# Sheet1.net
KiCad netlist of a schematic drawn in Altium Designer
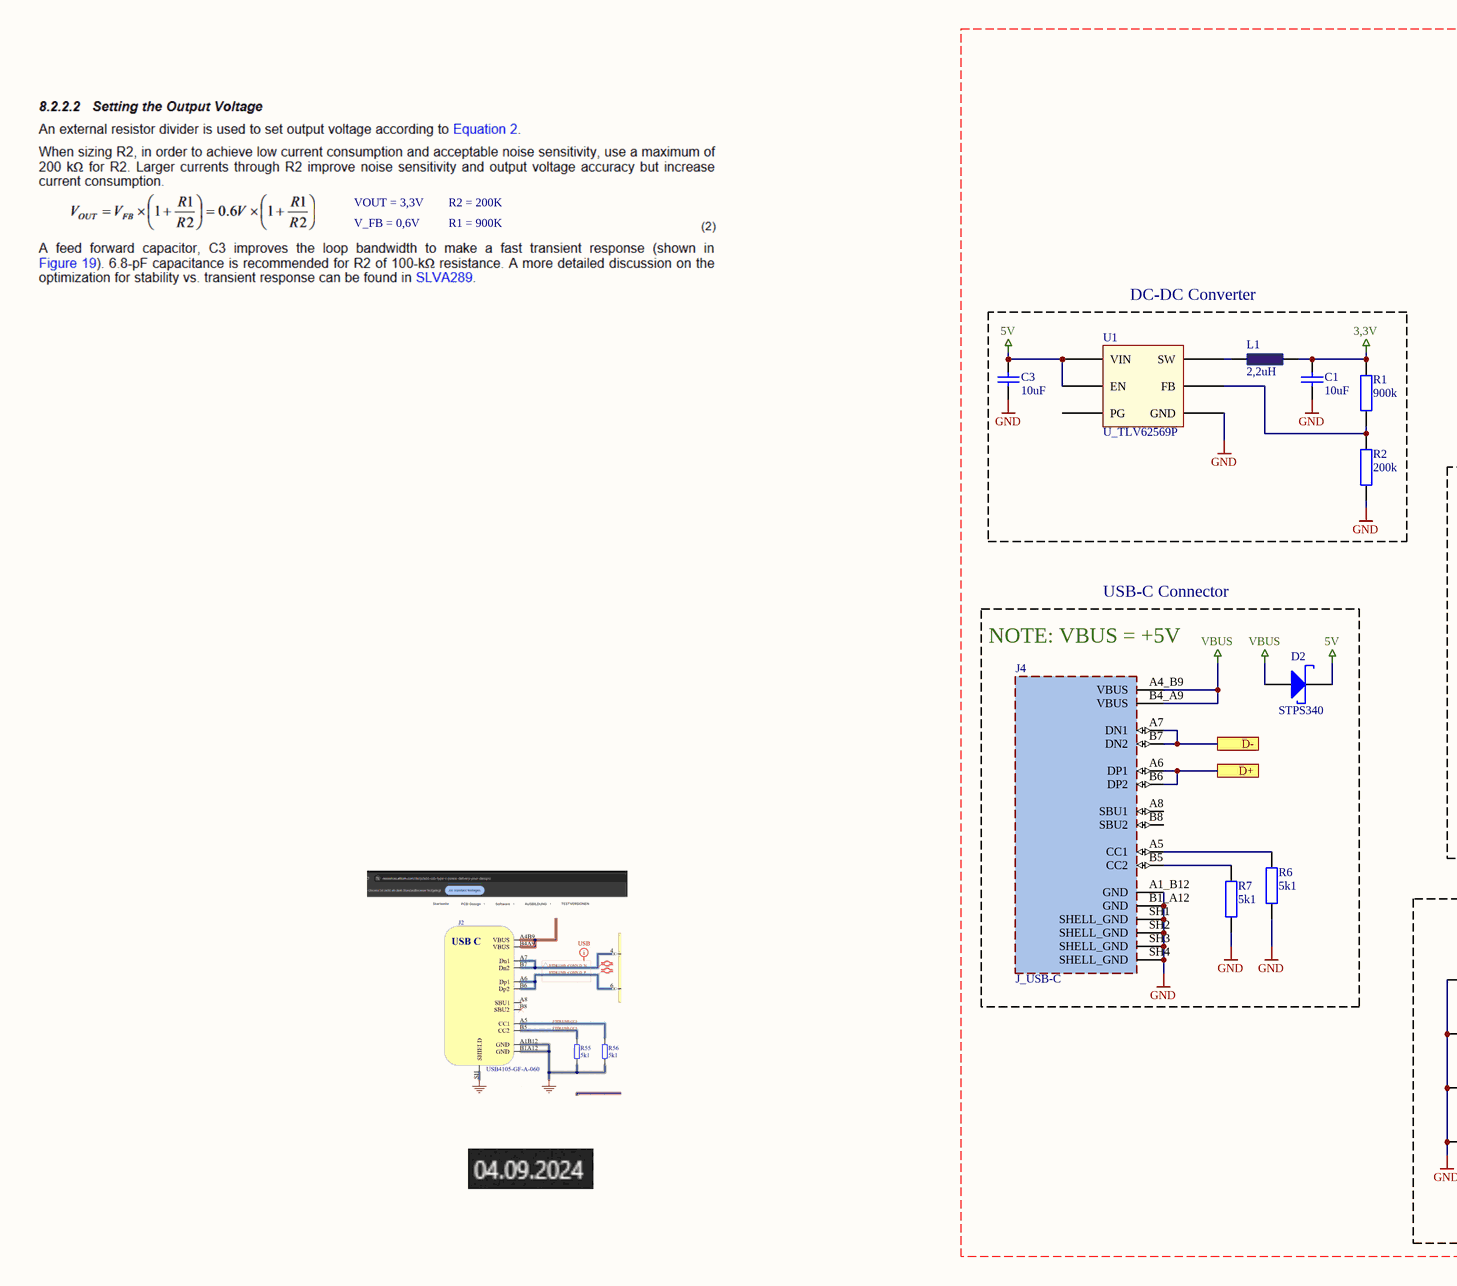
[diagram p0: Sheet1.SchDoc, left]
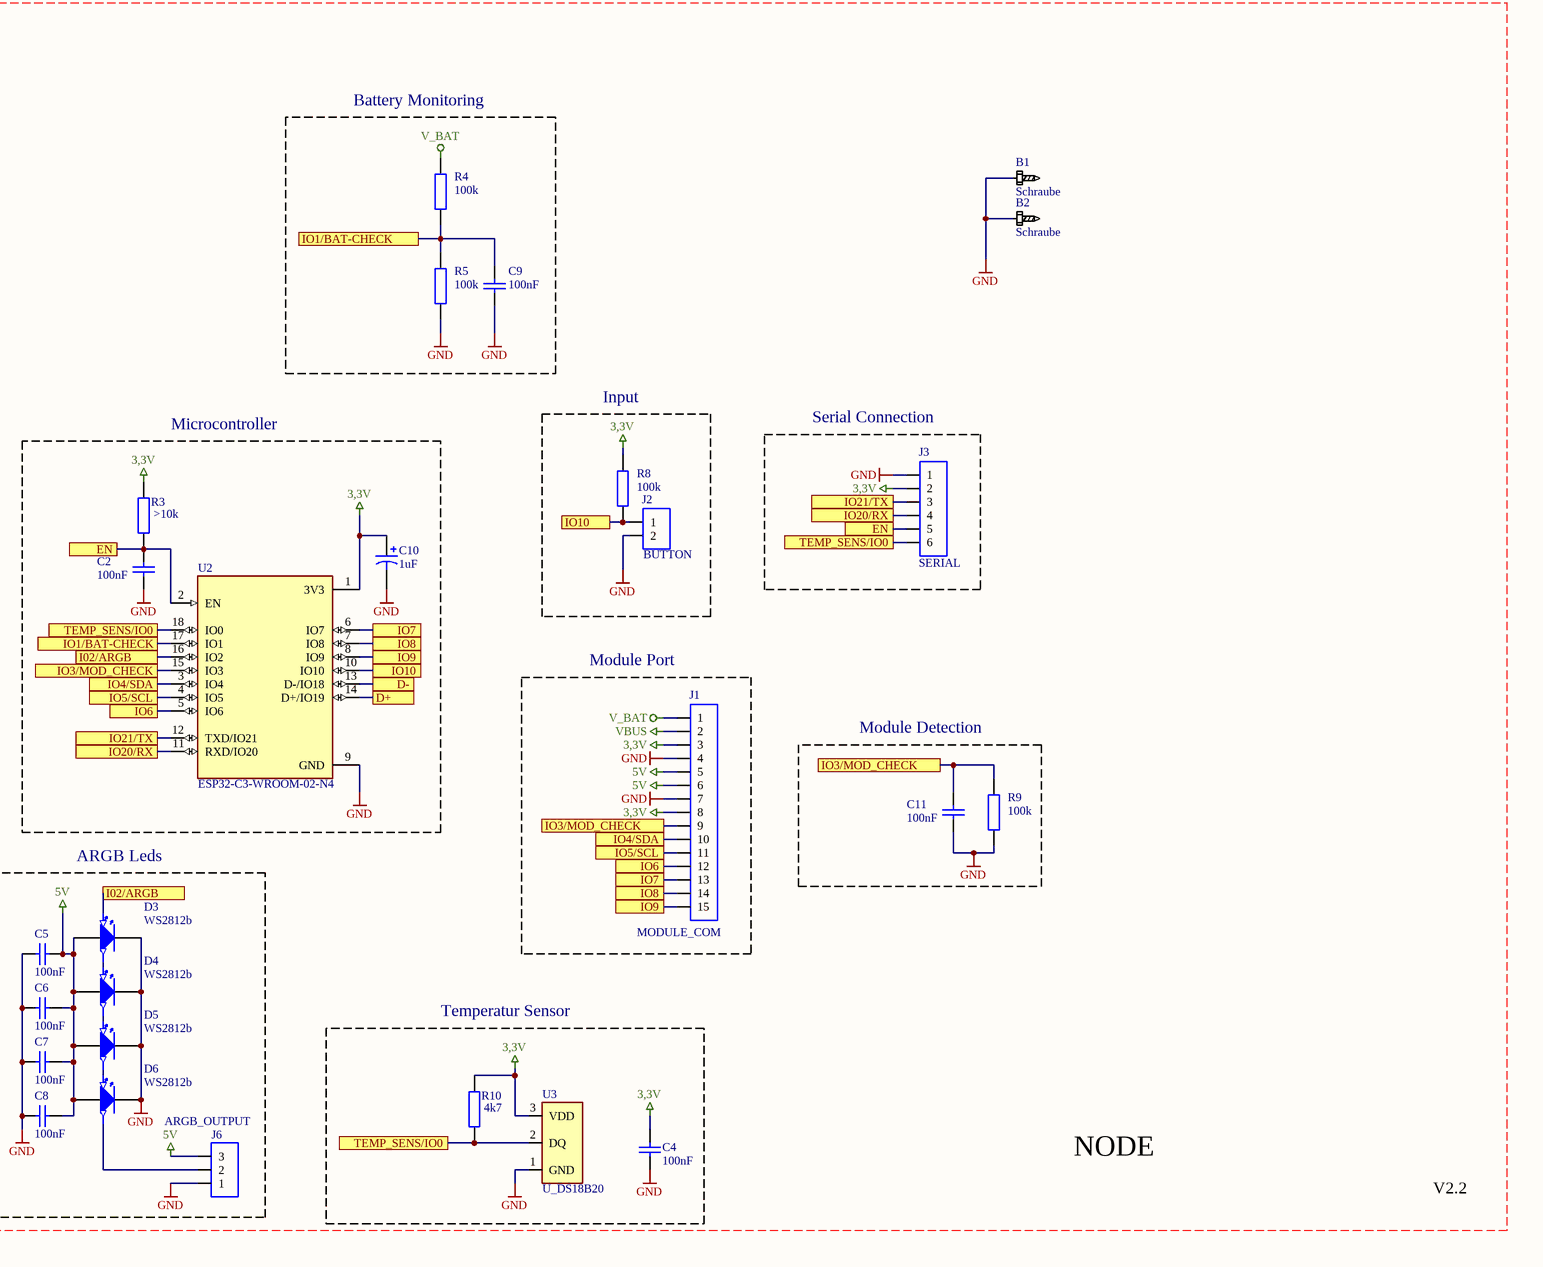
[diagram p1: Sheet1.SchDoc, right]

(export (version "E")
  (design (tool "Eeschema 10.0.6"))
  (components
    (comp (ref "B1")
      (value "Schraube")
      (footprint "B_Schraube-M3 PAD")
      (description "Schraubenloch für M3 Schrauben")
      (libsource (lib "SCHLIB-PCSB_5.1.3") (part "B_Schraube"))
    )
    (comp (ref "B2")
      (value "Schraube")
      (footprint "B_Schraube-M3 PAD")
      (description "Schraubenloch für M3 Schrauben")
      (libsource (lib "SCHLIB-PCSB_5.1.3") (part "B_Schraube"))
    )
    (comp (ref "C1")
      (value "10uF")
      (footprint "C_SMD_0805")
      (description "Kondensator SMD Universal, Keramik, Folie, usw.")
      (libsource (lib "SCHLIB-PCSB_5.1.3") (part "C_SMD_KO"))
    )
    (comp (ref "C2")
      (value "100nF")
      (footprint "C_SMD_0603")
      (description "Kondensator SMD Universal, Keramik, Folie, usw.")
      (libsource (lib "SCHLIB-PCSB_5.1.3") (part "C_SMD_KO"))
    )
    (comp (ref "C3")
      (value "10uF")
      (footprint "C_SMD_0805")
      (description "Kondensator SMD Universal, Keramik, Folie, usw.")
      (libsource (lib "SCHLIB-PCSB_5.1.3") (part "C_SMD_KO"))
    )
    (comp (ref "C4")
      (value "100nF")
      (footprint "C_SMD_0603")
      (description "Kondensator SMD Universal, Keramik, Folie, usw.")
      (libsource (lib "SCHLIB-PCSB_5.1.3") (part "C_SMD_KO"))
    )
    (comp (ref "C5")
      (value "100nF")
      (footprint "C_SMD_0603")
      (description "Kondensator SMD Universal, Keramik, Folie, usw.")
      (libsource (lib "SCHLIB-PCSB_5.1.3") (part "C_SMD_KO"))
    )
    (comp (ref "C6")
      (value "100nF")
      (footprint "C_SMD_0603")
      (description "Kondensator SMD Universal, Keramik, Folie, usw.")
      (libsource (lib "SCHLIB-PCSB_5.1.3") (part "C_SMD_KO"))
    )
    (comp (ref "C7")
      (value "100nF")
      (footprint "C_SMD_0603")
      (description "Kondensator SMD Universal, Keramik, Folie, usw.")
      (libsource (lib "SCHLIB-PCSB_5.1.3") (part "C_SMD_KO"))
    )
    (comp (ref "C8")
      (value "100nF")
      (footprint "C_SMD_0603")
      (description "Kondensator SMD Universal, Keramik, Folie, usw.")
      (libsource (lib "SCHLIB-PCSB_5.1.3") (part "C_SMD_KO"))
    )
    (comp (ref "C9")
      (value "100nF")
      (footprint "C_SMD_0603")
      (description "Kondensator SMD Universal, Keramik, Folie, usw.")
      (libsource (lib "SCHLIB-PCSB_5.1.3") (part "C_SMD_KO"))
    )
    (comp (ref "C10")
      (value "1uF")
      (footprint "C_SMD_0805")
      (description "Tantalkondensator")
      (libsource (lib "SCHLIB-PCSB_5.1.3") (part "C_SMD_Tantal"))
    )
    (comp (ref "C11")
      (value "100nF")
      (footprint "C_SMD_0603")
      (description "Kondensator SMD Universal, Keramik, Folie, usw.")
      (libsource (lib "SCHLIB-PCSB_5.1.3") (part "C_SMD_KO"))
    )
    (comp (ref "D2")
      (value "STPS340")
      (footprint "D_DO-221")
      (description "Diode SMD Schottky")
      (libsource (lib "SCHLIB-PCSB_5.1.3") (part "D_SMD_Schottky"))
    )
    (comp (ref "D3")
      (value "WS2812b")
      (footprint "D_SMD_LED-ARGB")
      (description "Diode SMD ARGB")
      (libsource (lib "SCHLIB-PCSB_5.1.3") (part "D_SMD_LED-ARGB"))
    )
    (comp (ref "D4")
      (value "WS2812b")
      (footprint "D_SMD_LED-ARGB")
      (description "Diode SMD ARGB")
      (libsource (lib "SCHLIB-PCSB_5.1.3") (part "D_SMD_LED-ARGB"))
    )
    (comp (ref "D5")
      (value "WS2812b")
      (footprint "D_SMD_LED-ARGB")
      (description "Diode SMD ARGB")
      (libsource (lib "SCHLIB-PCSB_5.1.3") (part "D_SMD_LED-ARGB"))
    )
    (comp (ref "D6")
      (value "WS2812b")
      (footprint "D_SMD_LED-ARGB")
      (description "Diode SMD ARGB")
      (libsource (lib "SCHLIB-PCSB_5.1.3") (part "D_SMD_LED-ARGB"))
    )
    (comp (ref "J1")
      (value "MODULE_COM")
      (footprint "SIP-15")
      (description "Stecker")
      (libsource (lib "SCHLIB-PCSB_5.1.3") (part "J_THT_CON15"))
    )
    (comp (ref "J2")
      (value "BUTTON")
      (footprint "SIP-2")
      (description "Stecker")
      (libsource (lib "SCHLIB-PCSB_5.1.3") (part "J_THT_CON2"))
    )
    (comp (ref "J3")
      (value "SERIAL")
      (footprint "SIP-6")
      (description "Stecker")
      (libsource (lib "SCHLIB-PCSB_5.1.3") (part "J_THT_CON6"))
    )
    (comp (ref "J4")
      (value "J_USB-C")
      (footprint "GCT_USB4105-GF-A")
      (description "USB4105-GF-")
      (fields (field (name "MF") "{'manufacturer': u'GCT'}") (field (name "MP") "USB4105-GF-A"))
      (libsource (lib "SCHLIB-PCSB_5.1.3") (part "J_USB-C"))
    )
    (comp (ref "J6")
      (value "ARGB_OUTPUT")
      (footprint "Sip-3")
      (description "Stecker")
      (libsource (lib "SCHLIB-PCSB_5.1.3") (part "J_THT_CON3"))
    )
    (comp (ref "L1")
      (value "2,2uH")
      (footprint "L_SMD_ND_NR3015T2R2M")
      (description "Spule SMD")
      (libsource (lib "SCHLIB-PCSB_5.1.3") (part "L_SMD_Spule"))
    )
    (comp (ref "R1")
      (value "900k")
      (footprint "R_SMD_0603")
      (description "Widerstand SMD")
      (libsource (lib "SCHLIB-PCSB_5.1.3") (part "R_SMD_Widerstand"))
    )
    (comp (ref "R2")
      (value "200k")
      (footprint "R_SMD_0603")
      (description "Widerstand SMD")
      (libsource (lib "SCHLIB-PCSB_5.1.3") (part "R_SMD_Widerstand"))
    )
    (comp (ref "R3")
      (value ">10k")
      (footprint "R_SMD_0805")
      (description "Widerstand SMD")
      (libsource (lib "SCHLIB-PCSB_5.1.3") (part "R_SMD_Widerstand"))
    )
    (comp (ref "R4")
      (value "100k")
      (footprint "R_SMD_0805")
      (description "Widerstand SMD")
      (libsource (lib "SCHLIB-PCSB_5.1.3") (part "R_SMD_Widerstand"))
    )
    (comp (ref "R5")
      (value "100k")
      (footprint "R_SMD_0805")
      (description "Widerstand SMD")
      (libsource (lib "SCHLIB-PCSB_5.1.3") (part "R_SMD_Widerstand"))
    )
    (comp (ref "R6")
      (value "5k1")
      (footprint "R_SMD_0805")
      (description "Widerstand SMD")
      (libsource (lib "SCHLIB-PCSB_5.1.3") (part "R_SMD_Widerstand"))
    )
    (comp (ref "R7")
      (value "5k1")
      (footprint "R_SMD_0805")
      (description "Widerstand SMD")
      (libsource (lib "SCHLIB-PCSB_5.1.3") (part "R_SMD_Widerstand"))
    )
    (comp (ref "R8")
      (value "100k")
      (footprint "R_SMD_0805")
      (description "Widerstand SMD")
      (libsource (lib "SCHLIB-PCSB_5.1.3") (part "R_SMD_Widerstand"))
    )
    (comp (ref "R9")
      (value "100k")
      (footprint "R_SMD_0805")
      (description "Widerstand SMD")
      (libsource (lib "SCHLIB-PCSB_5.1.3") (part "R_SMD_Widerstand"))
    )
    (comp (ref "R10")
      (value "4k7")
      (footprint "R_SMD_0603")
      (description "Widerstand SMD")
      (libsource (lib "SCHLIB-PCSB_5.1.3") (part "R_SMD_Widerstand"))
    )
    (comp (ref "U1")
      (value "U_TLV62569P")
      (footprint "SOT50P160X60-6N")
      (libsource (lib "SCHLIB-PCSB_5.1.3") (part "U_TLV62569P"))
    )
    (comp (ref "U2")
      (value "ESP32-C3-WROOM-02-N4")
      (footprint "MODULE_ESP32-C3-WROOM-02-H4")
      (fields (field (name "MF") "Espressif Systems"))
      (libsource (lib "SCHLIB-PCSB_5.1.3") (part "ESP32-C3-WROOM-02-N4"))
    )
    (comp (ref "U3")
      (value "U_DS18B20")
      (footprint "TO-92_DS18B20")
      (description "Temperature Sensor Digital, Local -55Â°C ~ 125Â°C 12 b 8-uMAX-EP¦8-uSOP-EP")
      (fields (field (name "MF") "Maxim") (field (name "MP") "DS18B20"))
      (libsource (lib "SCHLIB-PCSB_5.1.3") (part "U_DS18B20"))
    )
  )
  (nets
    (net (code "1") (name "/D+") (class "Default")
      (node (ref "J4") (pin "A6") (pinfunction "DP1_A6") (pintype "bidirectional"))
      (node (ref "J4") (pin "B6") (pinfunction "DP2_B6") (pintype "bidirectional"))
      (node (ref "U2") (pin "14") (pinfunction "D+/IO19_14") (pintype "bidirectional"))
    )
    (net (code "2") (name "/D-") (class "Default")
      (node (ref "J4") (pin "A7") (pinfunction "DN1_A7") (pintype "bidirectional"))
      (node (ref "J4") (pin "B7") (pinfunction "DN2_B7") (pintype "bidirectional"))
      (node (ref "U2") (pin "13") (pinfunction "D-/IO18_13") (pintype "bidirectional"))
    )
    (net (code "3") (name "/EN") (class "Default")
      (node (ref "C2") (pin "2") (pintype "passive"))
      (node (ref "J3") (pin "5") (pinfunction "5_5") (pintype "passive"))
      (node (ref "R3") (pin "1") (pintype "passive"))
      (node (ref "U2") (pin "2") (pinfunction "EN_2") (pintype "input"))
    )
    (net (code "4") (name "/I02{slash}ARGB") (class "Default")
      (node (ref "D3") (pin "4") (pinfunction "DIN_4") (pintype "input"))
      (node (ref "U2") (pin "16") (pinfunction "IO2_16") (pintype "bidirectional"))
    )
    (net (code "5") (name "/IO1{slash}BAT-CHECK") (class "Default")
      (node (ref "C9") (pin "2") (pintype "passive"))
      (node (ref "R4") (pin "1") (pintype "passive"))
      (node (ref "R5") (pin "2") (pintype "passive"))
      (node (ref "U2") (pin "17") (pinfunction "IO1_17") (pintype "bidirectional"))
    )
    (net (code "6") (name "/IO3{slash}MOD_CHECK") (class "Default")
      (node (ref "C11") (pin "2") (pintype "passive"))
      (node (ref "J1") (pin "9") (pinfunction "9_9") (pintype "passive"))
      (node (ref "R9") (pin "2") (pintype "passive"))
      (node (ref "U2") (pin "15") (pinfunction "IO3_15") (pintype "bidirectional"))
    )
    (net (code "7") (name "/IO4{slash}SDA") (class "Default")
      (node (ref "J1") (pin "10") (pinfunction "10_10") (pintype "passive"))
      (node (ref "U2") (pin "3") (pinfunction "IO4_3") (pintype "bidirectional"))
    )
    (net (code "8") (name "/IO5{slash}SCL") (class "Default")
      (node (ref "J1") (pin "11") (pinfunction "11_11") (pintype "passive"))
      (node (ref "U2") (pin "4") (pinfunction "IO5_4") (pintype "bidirectional"))
    )
    (net (code "9") (name "/IO6") (class "Default")
      (node (ref "J1") (pin "12") (pinfunction "12_12") (pintype "passive"))
      (node (ref "U2") (pin "5") (pinfunction "IO6_5") (pintype "bidirectional"))
    )
    (net (code "10") (name "/IO7") (class "Default")
      (node (ref "J1") (pin "13") (pinfunction "13_13") (pintype "passive"))
      (node (ref "U2") (pin "6") (pinfunction "IO7_6") (pintype "bidirectional"))
    )
    (net (code "11") (name "/IO8") (class "Default")
      (node (ref "J1") (pin "14") (pinfunction "14_14") (pintype "passive"))
      (node (ref "U2") (pin "7") (pinfunction "IO8_7") (pintype "bidirectional"))
    )
    (net (code "12") (name "/IO9") (class "Default")
      (node (ref "J1") (pin "15") (pinfunction "15_15") (pintype "passive"))
      (node (ref "U2") (pin "8") (pinfunction "IO9_8") (pintype "bidirectional"))
    )
    (net (code "13") (name "/IO10") (class "Default")
      (node (ref "J2") (pin "1") (pinfunction "1_1") (pintype "passive"))
      (node (ref "R8") (pin "1") (pintype "passive"))
      (node (ref "U2") (pin "10") (pinfunction "IO10_10") (pintype "bidirectional"))
    )
    (net (code "14") (name "/IO20{slash}RX") (class "Default")
      (node (ref "J3") (pin "4") (pinfunction "4_4") (pintype "passive"))
      (node (ref "U2") (pin "11") (pinfunction "RXD/IO20_11") (pintype "bidirectional"))
    )
    (net (code "15") (name "/IO21{slash}TX") (class "Default")
      (node (ref "J3") (pin "3") (pinfunction "3_3") (pintype "passive"))
      (node (ref "U2") (pin "12") (pinfunction "TXD/IO21_12") (pintype "bidirectional"))
    )
    (net (code "16") (name "/TEMP_SENS{slash}IO0") (class "Default")
      (node (ref "J3") (pin "6") (pinfunction "6_6") (pintype "passive"))
      (node (ref "R10") (pin "1") (pintype "passive"))
      (node (ref "U2") (pin "18") (pinfunction "IO0_18") (pintype "bidirectional"))
      (node (ref "U3") (pin "2") (pinfunction "DQ_2") (pintype "bidirectional"))
    )
    (net (code "17") (name "3,3V") (class "Default")
      (node (ref "C1") (pin "1") (pintype "passive"))
      (node (ref "C10") (pin "1") (pinfunction "1_1") (pintype "passive"))
      (node (ref "C4") (pin "1") (pintype "passive"))
      (node (ref "J1") (pin "3") (pinfunction "3_3") (pintype "passive"))
      (node (ref "J1") (pin "8") (pinfunction "8_8") (pintype "passive"))
      (node (ref "J3") (pin "2") (pinfunction "2_2") (pintype "passive"))
      (node (ref "L1") (pin "1") (pintype "passive"))
      (node (ref "R1") (pin "1") (pintype "passive"))
      (node (ref "R10") (pin "2") (pintype "passive"))
      (node (ref "R3") (pin "2") (pintype "passive"))
      (node (ref "R8") (pin "2") (pintype "passive"))
      (node (ref "U2") (pin "1") (pinfunction "3V3_1") (pintype "power_in"))
      (node (ref "U3") (pin "3") (pinfunction "VDD_3") (pintype "power_in"))
    )
    (net (code "18") (name "5V") (class "Default")
      (node (ref "C3") (pin "1") (pintype "passive"))
      (node (ref "C5") (pin "2") (pintype "passive"))
      (node (ref "C6") (pin "2") (pintype "passive"))
      (node (ref "C7") (pin "2") (pintype "passive"))
      (node (ref "C8") (pin "2") (pintype "passive"))
      (node (ref "D2") (pin "2") (pinfunction "K_2") (pintype "passive"))
      (node (ref "D3") (pin "1") (pinfunction "VDD_1") (pintype "passive"))
      (node (ref "D4") (pin "1") (pinfunction "VDD_1") (pintype "passive"))
      (node (ref "D5") (pin "1") (pinfunction "VDD_1") (pintype "passive"))
      (node (ref "D6") (pin "1") (pinfunction "VDD_1") (pintype "passive"))
      (node (ref "J1") (pin "5") (pinfunction "5_5") (pintype "passive"))
      (node (ref "J1") (pin "6") (pinfunction "6_6") (pintype "passive"))
      (node (ref "J6") (pin "3") (pinfunction "3_3") (pintype "passive"))
      (node (ref "U1") (pin "3") (pinfunction "VIN_3") (pintype "passive"))
      (node (ref "U1") (pin "5") (pinfunction "EN_5") (pintype "passive"))
    )
    (net (code "19") (name "GND") (class "Default")
      (node (ref "B1") (pin "1") (pinfunction "PAD_1") (pintype "passive"))
      (node (ref "B2") (pin "1") (pinfunction "PAD_1") (pintype "passive"))
      (node (ref "C1") (pin "2") (pintype "passive"))
      (node (ref "C10") (pin "2") (pinfunction "2_2") (pintype "passive"))
      (node (ref "C11") (pin "1") (pintype "passive"))
      (node (ref "C2") (pin "1") (pintype "passive"))
      (node (ref "C3") (pin "2") (pintype "passive"))
      (node (ref "C4") (pin "2") (pintype "passive"))
      (node (ref "C5") (pin "1") (pintype "passive"))
      (node (ref "C6") (pin "1") (pintype "passive"))
      (node (ref "C7") (pin "1") (pintype "passive"))
      (node (ref "C8") (pin "1") (pintype "passive"))
      (node (ref "C9") (pin "1") (pintype "passive"))
      (node (ref "D3") (pin "3") (pinfunction "GND_3") (pintype "passive"))
      (node (ref "D4") (pin "3") (pinfunction "GND_3") (pintype "passive"))
      (node (ref "D5") (pin "3") (pinfunction "GND_3") (pintype "passive"))
      (node (ref "D6") (pin "3") (pinfunction "GND_3") (pintype "passive"))
      (node (ref "J1") (pin "4") (pinfunction "4_4") (pintype "passive"))
      (node (ref "J1") (pin "7") (pinfunction "7_7") (pintype "passive"))
      (node (ref "J2") (pin "2") (pinfunction "2_2") (pintype "passive"))
      (node (ref "J3") (pin "1") (pinfunction "1_1") (pintype "passive"))
      (node (ref "J4") (pin "A1_B12") (pinfunction "GND_A1_B12") (pintype "power_in"))
      (node (ref "J4") (pin "B1_A12") (pinfunction "GND_B1_A12") (pintype "power_in"))
      (node (ref "J4") (pin "SH1") (pinfunction "SHELL_GND_SH1") (pintype "power_in"))
      (node (ref "J4") (pin "SH2") (pinfunction "SHELL_GND_SH2") (pintype "power_in"))
      (node (ref "J4") (pin "SH3") (pinfunction "SHELL_GND_SH3") (pintype "power_in"))
      (node (ref "J4") (pin "SH4") (pinfunction "SHELL_GND_SH4") (pintype "power_in"))
      (node (ref "J6") (pin "1") (pinfunction "1_1") (pintype "passive"))
      (node (ref "R2") (pin "2") (pintype "passive"))
      (node (ref "R5") (pin "1") (pintype "passive"))
      (node (ref "R6") (pin "1") (pintype "passive"))
      (node (ref "R7") (pin "1") (pintype "passive"))
      (node (ref "R9") (pin "1") (pintype "passive"))
      (node (ref "U1") (pin "2") (pinfunction "GND_2") (pintype "passive"))
      (node (ref "U2") (pin "9") (pinfunction "GND_9") (pintype "power_in"))
      (node (ref "U3") (pin "1") (pinfunction "GND_1") (pintype "power_in"))
    )
    (net (code "20") (name "Net-(D3-DOUT)") (class "Default")
      (node (ref "D3") (pin "2") (pinfunction "DOUT_2") (pintype "output"))
      (node (ref "D4") (pin "4") (pinfunction "DIN_4") (pintype "input"))
    )
    (net (code "21") (name "Net-(D4-DOUT)") (class "Default")
      (node (ref "D4") (pin "2") (pinfunction "DOUT_2") (pintype "output"))
      (node (ref "D5") (pin "4") (pinfunction "DIN_4") (pintype "input"))
    )
    (net (code "22") (name "Net-(D5-DOUT)") (class "Default")
      (node (ref "D5") (pin "2") (pinfunction "DOUT_2") (pintype "output"))
      (node (ref "D6") (pin "4") (pinfunction "DIN_4") (pintype "input"))
    )
    (net (code "23") (name "Net-(D6-DOUT)") (class "Default")
      (node (ref "D6") (pin "2") (pinfunction "DOUT_2") (pintype "output"))
      (node (ref "J6") (pin "2") (pinfunction "2_2") (pintype "passive"))
    )
    (net (code "24") (name "Net-(J4-CC1)") (class "Default")
      (node (ref "J4") (pin "A5") (pinfunction "CC1_A5") (pintype "bidirectional"))
      (node (ref "R6") (pin "2") (pintype "passive"))
    )
    (net (code "25") (name "Net-(J4-CC2)") (class "Default")
      (node (ref "J4") (pin "B5") (pinfunction "CC2_B5") (pintype "bidirectional"))
      (node (ref "R7") (pin "2") (pintype "passive"))
    )
    (net (code "26") (name "Net-(U1-FB)") (class "Default")
      (node (ref "R1") (pin "2") (pintype "passive"))
      (node (ref "R2") (pin "1") (pintype "passive"))
      (node (ref "U1") (pin "1") (pinfunction "FB_1") (pintype "passive"))
    )
    (net (code "27") (name "Net-(U1-SW)") (class "Default")
      (node (ref "L1") (pin "2") (pintype "passive"))
      (node (ref "U1") (pin "4") (pinfunction "SW_4") (pintype "passive"))
    )
    (net (code "28") (name "VBUS") (class "Default")
      (node (ref "D2") (pin "1") (pinfunction "A_1") (pintype "passive"))
      (node (ref "J1") (pin "2") (pinfunction "2_2") (pintype "passive"))
      (node (ref "J4") (pin "A4_B9") (pinfunction "VBUS_A4_B9") (pintype "power_in"))
      (node (ref "J4") (pin "B4_A9") (pinfunction "VBUS_B4_A9") (pintype "power_in"))
    )
    (net (code "29") (name "V_BAT") (class "Default")
      (node (ref "J1") (pin "1") (pinfunction "1_1") (pintype "passive"))
      (node (ref "R4") (pin "2") (pintype "passive"))
    )
    (net (code "30") (name "unconnected-(J4-SBU1-PadA8)") (class "Default")
      (node (ref "J4") (pin "A8") (pinfunction "SBU1_A8") (pintype "bidirectional"))
    )
    (net (code "31") (name "unconnected-(J4-SBU2-PadB8)") (class "Default")
      (node (ref "J4") (pin "B8") (pinfunction "SBU2_B8") (pintype "bidirectional"))
    )
    (net (code "32") (name "unconnected-(U1-PG-Pad6)") (class "Default")
      (node (ref "U1") (pin "6") (pinfunction "PG_6") (pintype "passive"))
    )
  )
)
